# Clock.net
KiCad netlist of a schematic drawn in EAGLE
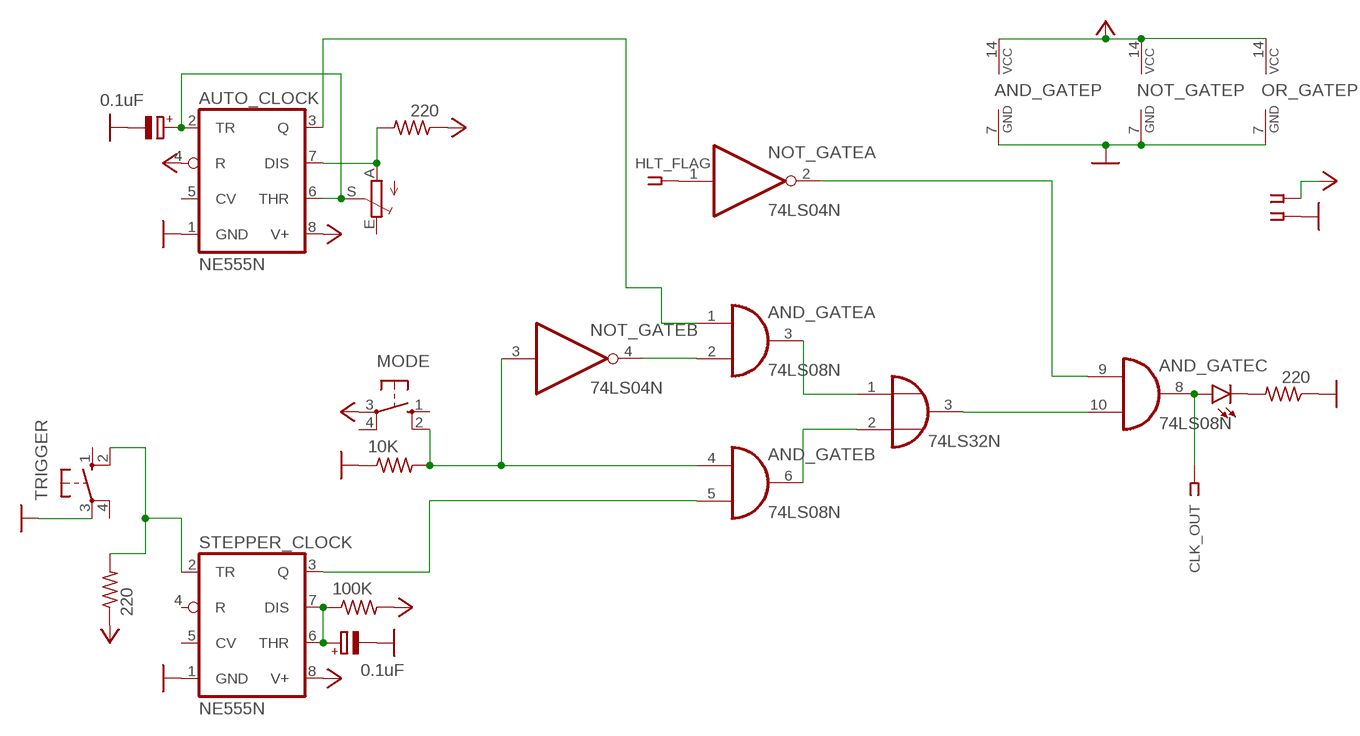
[diagram p0: schematic, sheet 1]

(export (version "E")
  (design (tool "Eeschema 10.0.6"))
  (components
    (comp (ref "AND_GATE")
      (value "74LS08N")
      (footprint "eagle-import:DIL14")
      (libsource (lib "eagle-import") (part "7408NLS"))
    )
    (comp (ref "AUTO_CLOCK")
      (value "NE555N")
      (footprint "eagle-import:DIL08")
      (libsource (lib "eagle-import") (part "555NNE"))
    )
    (comp (ref "C1")
      (value "0.1uF")
      (footprint "eagle-import:E2-5")
      (libsource (lib "eagle-import") (part "CPOL-EUE2-5"))
    )
    (comp (ref "C2")
      (value "0.1uF")
      (footprint "eagle-import:E2-5")
      (libsource (lib "eagle-import") (part "CPOL-EUE2-5"))
    )
    (comp (ref "CLK_OUT")
      (value "SSW-101-02-G-S-RA")
      (footprint "eagle-import:SSW-101-02-G-S-RA")
      (fields (field (name "MF") "Samtec Inc."))
      (libsource (lib "eagle-import") (part "SSW-101-02-G-S-RA"))
    )
    (comp (ref "CLOCK")
      (value "LED5MM")
      (footprint "eagle-import:LED5MM")
      (libsource (lib "eagle-import") (part "LED5MM"))
    )
    (comp (ref "FREQUENCY")
      (value "TRIM_EU-RJ9W")
      (footprint "eagle-import:RJ9W")
      (libsource (lib "eagle-import") (part "TRIM_EU-RJ9W"))
    )
    (comp (ref "GND")
      (value "SSW-101-02-G-S-RA")
      (footprint "eagle-import:SSW-101-02-G-S-RA")
      (fields (field (name "MF") "Samtec Inc."))
      (libsource (lib "eagle-import") (part "SSW-101-02-G-S-RA"))
    )
    (comp (ref "HLT_FLAG")
      (value "SSW-101-02-G-S-RA")
      (footprint "eagle-import:SSW-101-02-G-S-RA")
      (fields (field (name "MF") "Samtec Inc."))
      (libsource (lib "eagle-import") (part "SSW-101-02-G-S-RA"))
    )
    (comp (ref "MODE")
      (value "10-XX")
      (footprint "eagle-import:B3F-10XX")
      (fields (field (name "MPN") "B3F-1000"))
      (libsource (lib "eagle-import") (part "10-XX"))
    )
    (comp (ref "NOT_GATE")
      (value "74LS04N")
      (footprint "eagle-import:DIL14")
      (libsource (lib "eagle-import") (part "7404NLS"))
    )
    (comp (ref "OR_GATE")
      (value "74LS32N")
      (footprint "eagle-import:DIL14")
      (libsource (lib "eagle-import") (part "7432NLS"))
    )
    (comp (ref "R2")
      (value "220")
      (footprint "eagle-import:0204_7")
      (libsource (lib "eagle-import") (part "R-US_0204/7"))
    )
    (comp (ref "R3")
      (value "100K")
      (footprint "eagle-import:0204_7")
      (libsource (lib "eagle-import") (part "R-US_0204/7"))
    )
    (comp (ref "R4")
      (value "10K")
      (footprint "eagle-import:0204_7")
      (libsource (lib "eagle-import") (part "R-US_0204/7"))
    )
    (comp (ref "R5")
      (value "220")
      (footprint "eagle-import:0204_7")
      (libsource (lib "eagle-import") (part "R-US_0204/7"))
    )
    (comp (ref "R6")
      (value "220")
      (footprint "eagle-import:0204_7")
      (libsource (lib "eagle-import") (part "R-US_0204/7"))
    )
    (comp (ref "STEPPER_CLOCK")
      (value "NE555N")
      (footprint "eagle-import:DIL08")
      (libsource (lib "eagle-import") (part "555NNE"))
    )
    (comp (ref "TRIGGER")
      (value "10-XX")
      (footprint "eagle-import:B3F-10XX")
      (fields (field (name "MPN") "B3F-1000"))
      (libsource (lib "eagle-import") (part "10-XX"))
    )
    (comp (ref "VCC")
      (value "SSW-101-02-G-S-RA")
      (footprint "eagle-import:SSW-101-02-G-S-RA")
      (fields (field (name "MF") "Samtec Inc."))
      (libsource (lib "eagle-import") (part "SSW-101-02-G-S-RA"))
    )
  )
  (nets
    (net (code "1") (name "+5V") (class "Default")
      (node (ref "AND_GATE") (pin "14") (pinfunction "VCC_14") (pintype "power_in"))
      (node (ref "AUTO_CLOCK") (pin "4") (pinfunction "R_4") (pintype "input"))
      (node (ref "AUTO_CLOCK") (pin "8") (pinfunction "V+_8") (pintype "power_in"))
      (node (ref "MODE") (pin "3") (pinfunction "P_3") (pintype "passive"))
      (node (ref "NOT_GATE") (pin "14") (pinfunction "VCC_14") (pintype "power_in"))
      (node (ref "OR_GATE") (pin "14") (pinfunction "VCC_14") (pintype "power_in"))
      (node (ref "R2") (pin "1") (pinfunction "1_1") (pintype "passive"))
      (node (ref "R3") (pin "2") (pinfunction "2_2") (pintype "passive"))
      (node (ref "R6") (pin "1") (pinfunction "1_1") (pintype "passive"))
      (node (ref "STEPPER_CLOCK") (pin "8") (pinfunction "V+_8") (pintype "power_in"))
      (node (ref "VCC") (pin "1") (pinfunction "1_1") (pintype "passive"))
    )
    (net (code "2") (name "GND") (class "Default")
      (node (ref "AND_GATE") (pin "7") (pinfunction "GND_7") (pintype "power_in"))
      (node (ref "AUTO_CLOCK") (pin "1") (pinfunction "GND_1") (pintype "power_in"))
      (node (ref "C1") (pin "-") (pinfunction "-_-") (pintype "passive"))
      (node (ref "C2") (pin "-") (pinfunction "-_-") (pintype "passive"))
      (node (ref "GND") (pin "1") (pinfunction "1_1") (pintype "passive"))
      (node (ref "NOT_GATE") (pin "7") (pinfunction "GND_7") (pintype "power_in"))
      (node (ref "OR_GATE") (pin "7") (pinfunction "GND_7") (pintype "power_in"))
      (node (ref "R4") (pin "1") (pinfunction "1_1") (pintype "passive"))
      (node (ref "R5") (pin "1") (pinfunction "1_1") (pintype "passive"))
      (node (ref "STEPPER_CLOCK") (pin "1") (pinfunction "GND_1") (pintype "power_in"))
      (node (ref "TRIGGER") (pin "3") (pinfunction "P_3") (pintype "passive"))
    )
    (net (code "3") (name "Net-(AND_GATEA-I0)") (class "Default")
      (node (ref "AND_GATE") (pin "1") (pinfunction "I0_1") (pintype "input"))
      (node (ref "AUTO_CLOCK") (pin "3") (pinfunction "Q_3") (pintype "output"))
    )
    (net (code "4") (name "Net-(AND_GATEA-I1)") (class "Default")
      (node (ref "AND_GATE") (pin "2") (pinfunction "I1_2") (pintype "input"))
      (node (ref "NOT_GATE") (pin "4") (pinfunction "O_4") (pintype "output"))
    )
    (net (code "5") (name "Net-(AND_GATEA-O)") (class "Default")
      (node (ref "AND_GATE") (pin "3") (pinfunction "O_3") (pintype "output"))
      (node (ref "OR_GATE") (pin "1") (pinfunction "I0_1") (pintype "input"))
    )
    (net (code "6") (name "Net-(AND_GATEB-I0)") (class "Default")
      (node (ref "AND_GATE") (pin "4") (pinfunction "I0_4") (pintype "input"))
      (node (ref "MODE") (pin "2") (pinfunction "S1_2") (pintype "passive"))
      (node (ref "NOT_GATE") (pin "3") (pinfunction "I_3") (pintype "input"))
      (node (ref "R4") (pin "2") (pinfunction "2_2") (pintype "passive"))
    )
    (net (code "7") (name "Net-(AND_GATEB-I1)") (class "Default")
      (node (ref "AND_GATE") (pin "5") (pinfunction "I1_5") (pintype "input"))
      (node (ref "STEPPER_CLOCK") (pin "3") (pinfunction "Q_3") (pintype "output"))
    )
    (net (code "8") (name "Net-(AND_GATEB-O)") (class "Default")
      (node (ref "AND_GATE") (pin "6") (pinfunction "O_6") (pintype "output"))
      (node (ref "OR_GATE") (pin "2") (pinfunction "I1_2") (pintype "input"))
    )
    (net (code "9") (name "Net-(AND_GATEC-I0)") (class "Default")
      (node (ref "AND_GATE") (pin "9") (pinfunction "I0_9") (pintype "input"))
      (node (ref "NOT_GATE") (pin "2") (pinfunction "O_2") (pintype "output"))
    )
    (net (code "10") (name "Net-(AND_GATEC-I1)") (class "Default")
      (node (ref "AND_GATE") (pin "10") (pinfunction "I1_10") (pintype "input"))
      (node (ref "OR_GATE") (pin "3") (pinfunction "O_3") (pintype "output"))
    )
    (net (code "11") (name "Net-(AND_GATEC-O)") (class "Default")
      (node (ref "AND_GATE") (pin "8") (pinfunction "O_8") (pintype "output"))
      (node (ref "CLK_OUT") (pin "1") (pinfunction "1_1") (pintype "passive"))
      (node (ref "CLOCK") (pin "A") (pinfunction "A_A") (pintype "passive"))
    )
    (net (code "12") (name "Net-(AUTO_CLOCK-DIS)") (class "Default")
      (node (ref "AUTO_CLOCK") (pin "7") (pinfunction "DIS_7") (pintype "input"))
      (node (ref "FREQUENCY") (pin "A") (pinfunction "A_A") (pintype "passive"))
      (node (ref "R6") (pin "2") (pinfunction "2_2") (pintype "passive"))
    )
    (net (code "13") (name "Net-(AUTO_CLOCK-THR)") (class "Default")
      (node (ref "AUTO_CLOCK") (pin "2") (pinfunction "TR_2") (pintype "input"))
      (node (ref "AUTO_CLOCK") (pin "6") (pinfunction "THR_6") (pintype "input"))
      (node (ref "C1") (pin "+") (pinfunction "+_+") (pintype "passive"))
      (node (ref "FREQUENCY") (pin "S") (pinfunction "S_S") (pintype "passive"))
    )
    (net (code "14") (name "Net-(CLOCK-C)") (class "Default")
      (node (ref "CLOCK") (pin "K") (pinfunction "C_K") (pintype "passive"))
      (node (ref "R5") (pin "2") (pinfunction "2_2") (pintype "passive"))
    )
    (net (code "15") (name "Net-(NOT_GATEA-I)") (class "Default")
      (node (ref "HLT_FLAG") (pin "1") (pinfunction "1_1") (pintype "passive"))
      (node (ref "NOT_GATE") (pin "1") (pinfunction "I_1") (pintype "input"))
    )
    (net (code "16") (name "Net-(STEPPER_CLOCK-DIS)") (class "Default")
      (node (ref "C2") (pin "+") (pinfunction "+_+") (pintype "passive"))
      (node (ref "R3") (pin "1") (pinfunction "1_1") (pintype "passive"))
      (node (ref "STEPPER_CLOCK") (pin "6") (pinfunction "THR_6") (pintype "input"))
      (node (ref "STEPPER_CLOCK") (pin "7") (pinfunction "DIS_7") (pintype "input"))
    )
    (net (code "17") (name "Net-(STEPPER_CLOCK-TR)") (class "Default")
      (node (ref "R2") (pin "2") (pinfunction "2_2") (pintype "passive"))
      (node (ref "STEPPER_CLOCK") (pin "2") (pinfunction "TR_2") (pintype "input"))
      (node (ref "TRIGGER") (pin "2") (pinfunction "S1_2") (pintype "passive"))
    )
    (net (code "18") (name "unconnected-(AUTO_CLOCK-CV-Pad5)") (class "Default")
      (node (ref "AUTO_CLOCK") (pin "5") (pinfunction "CV_5") (pintype "input"))
    )
    (net (code "19") (name "unconnected-(FREQUENCY-PadE)") (class "Default")
      (node (ref "FREQUENCY") (pin "E") (pinfunction "E_E") (pintype "passive"))
    )
    (net (code "20") (name "unconnected-(MODE-P1-Pad4)") (class "Default")
      (node (ref "MODE") (pin "4") (pinfunction "P1_4") (pintype "passive"))
    )
    (net (code "21") (name "unconnected-(MODE-S-Pad1)") (class "Default")
      (node (ref "MODE") (pin "1") (pinfunction "S_1") (pintype "passive"))
    )
    (net (code "22") (name "unconnected-(STEPPER_CLOCK-CV-Pad5)") (class "Default")
      (node (ref "STEPPER_CLOCK") (pin "5") (pinfunction "CV_5") (pintype "input"))
    )
    (net (code "23") (name "unconnected-(STEPPER_CLOCK-R-Pad4)") (class "Default")
      (node (ref "STEPPER_CLOCK") (pin "4") (pinfunction "R_4") (pintype "input"))
    )
    (net (code "24") (name "unconnected-(TRIGGER-P1-Pad4)") (class "Default")
      (node (ref "TRIGGER") (pin "4") (pinfunction "P1_4") (pintype "passive"))
    )
    (net (code "25") (name "unconnected-(TRIGGER-S-Pad1)") (class "Default")
      (node (ref "TRIGGER") (pin "1") (pinfunction "S_1") (pintype "passive"))
    )
  )
)
